# ATtinyTrafficLight.net
KiCad netlist of a schematic drawn in EAGLE
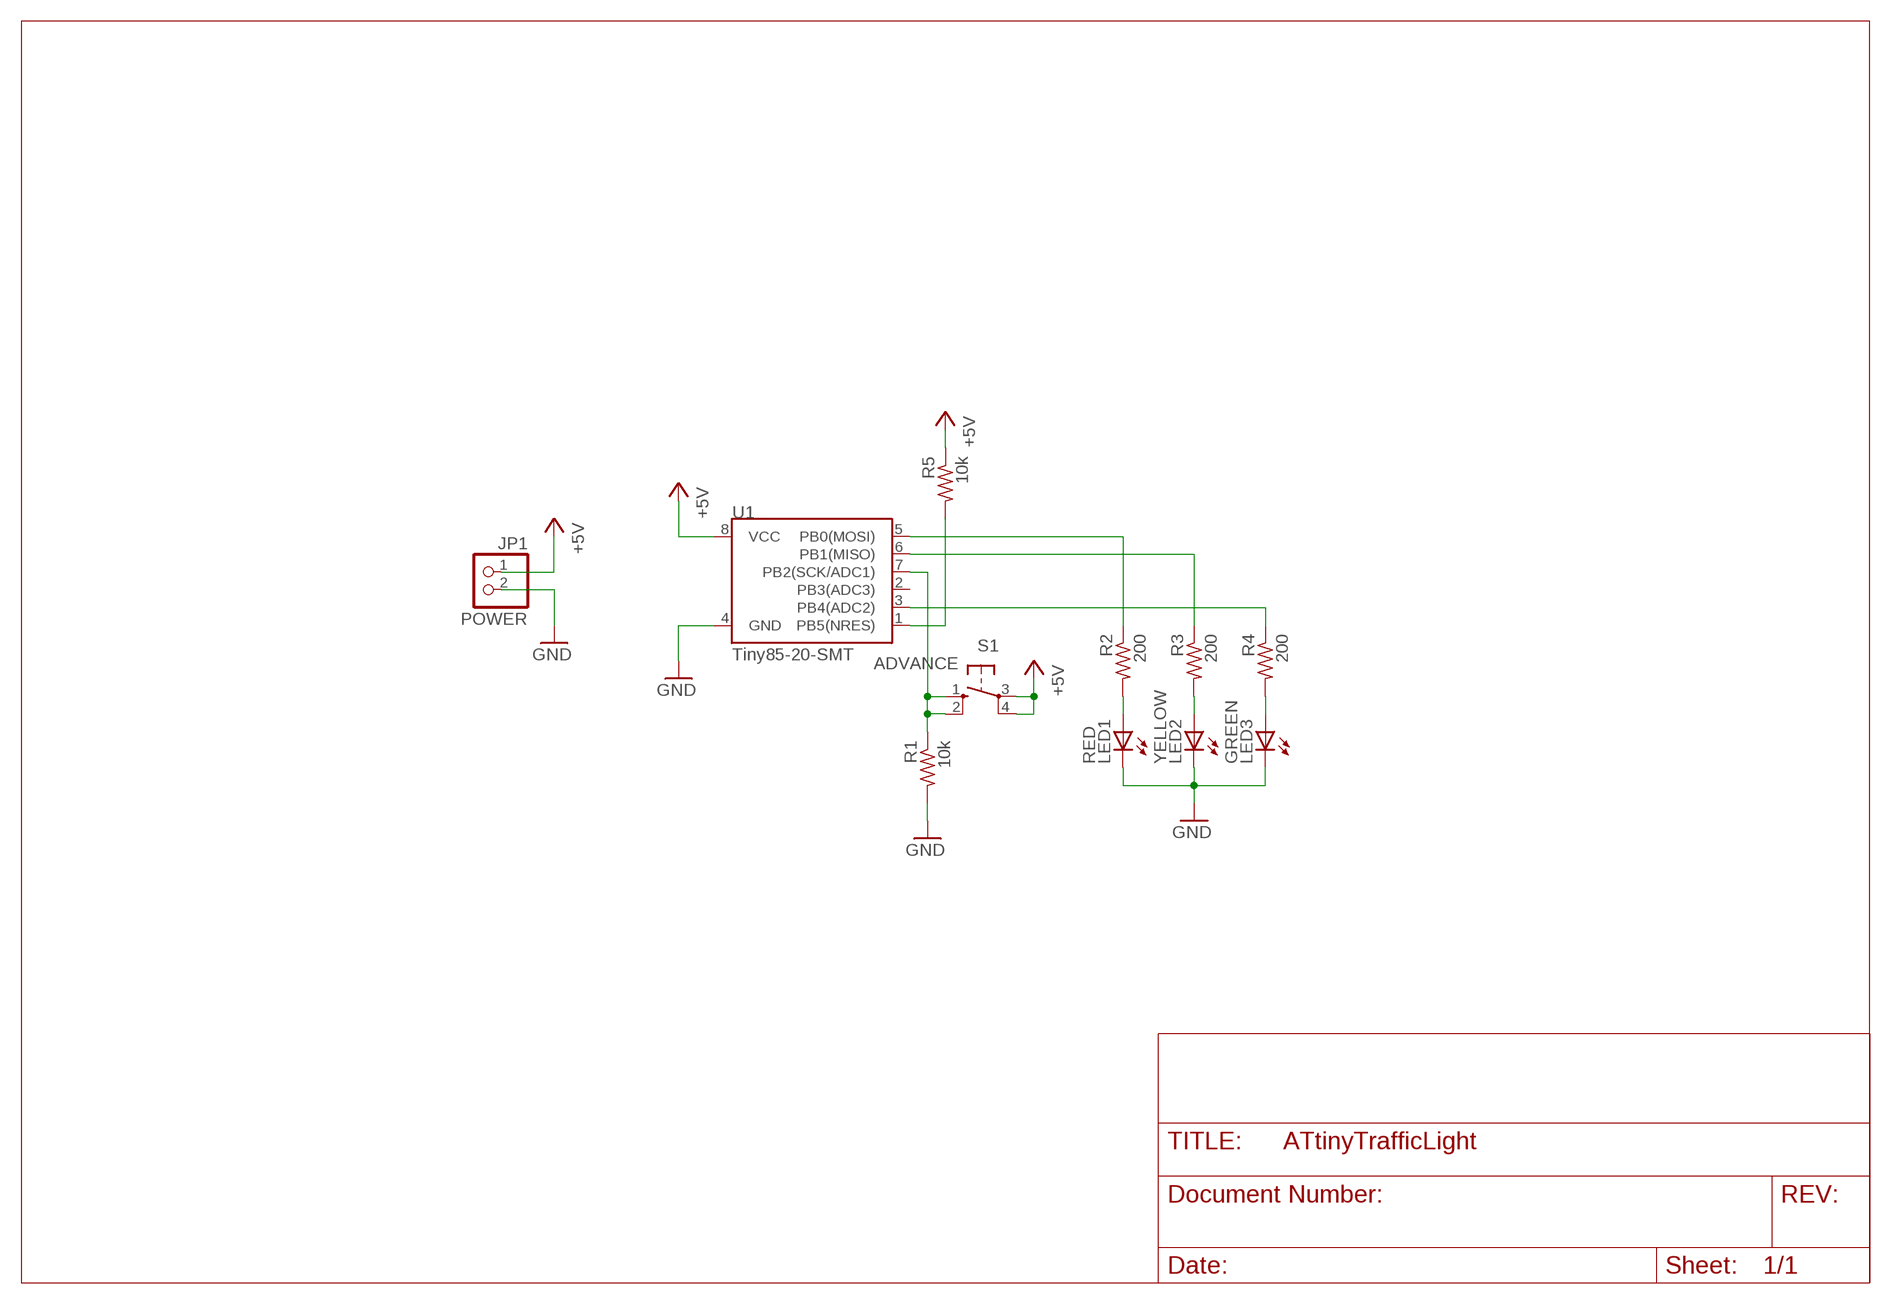
[diagram p0: schematic, sheet 1]

(export (version "E")
  (design (tool "Eeschema 10.0.6"))
  (components
    (comp (ref "JP1")
      (value "POWER")
      (footprint "eagle-import:1X02")
      (libsource (lib "eagle-import") (part "PINHD-1X2"))
    )
    (comp (ref "LED1")
      (value "RED")
      (footprint "eagle-import:CHIPLED_0805")
      (libsource (lib "eagle-import") (part "LEDCHIPLED_0805"))
    )
    (comp (ref "LED2")
      (value "YELLOW")
      (footprint "eagle-import:CHIPLED_0805")
      (libsource (lib "eagle-import") (part "LEDCHIPLED_0805"))
    )
    (comp (ref "LED3")
      (value "GREEN")
      (footprint "eagle-import:CHIPLED_0805")
      (libsource (lib "eagle-import") (part "LEDCHIPLED_0805"))
    )
    (comp (ref "R1")
      (value "10k")
      (footprint "eagle-import:R0805")
      (libsource (lib "eagle-import") (part "R-US_R0805"))
    )
    (comp (ref "R2")
      (value "200")
      (footprint "eagle-import:R0805")
      (libsource (lib "eagle-import") (part "R-US_R0805"))
    )
    (comp (ref "R3")
      (value "200")
      (footprint "eagle-import:R0805")
      (libsource (lib "eagle-import") (part "R-US_R0805"))
    )
    (comp (ref "R4")
      (value "200")
      (footprint "eagle-import:R0805")
      (libsource (lib "eagle-import") (part "R-US_R0805"))
    )
    (comp (ref "R5")
      (value "10k")
      (footprint "eagle-import:R0805")
      (libsource (lib "eagle-import") (part "R-US_R0805"))
    )
    (comp (ref "S1")
      (value "ADVANCE")
      (footprint "eagle-import:B3F-10XX")
      (fields (field (name "MPN") "B3F-1000"))
      (libsource (lib "eagle-import") (part "10-XX"))
    )
    (comp (ref "U1")
      (value "Tiny85-20-SMT")
      (footprint "eagle-import:SO08-EIAJ")
      (libsource (lib "eagle-import") (part "ATTINY45TINY85-20-SMT"))
    )
  )
  (nets
    (net (code "1") (name "+5V") (class "Default")
      (node (ref "JP1") (pin "1") (pinfunction "1_1") (pintype "passive"))
      (node (ref "R5") (pin "1") (pinfunction "1_1") (pintype "passive"))
      (node (ref "S1") (pin "3") (pinfunction "P_3") (pintype "passive"))
      (node (ref "S1") (pin "4") (pinfunction "P1_4") (pintype "passive"))
      (node (ref "U1") (pin "8") (pinfunction "VCC_8") (pintype "bidirectional"))
    )
    (net (code "2") (name "GND") (class "Default")
      (node (ref "JP1") (pin "2") (pinfunction "2_2") (pintype "passive"))
      (node (ref "LED1") (pin "C") (pinfunction "C_C") (pintype "passive"))
      (node (ref "LED2") (pin "C") (pinfunction "C_C") (pintype "passive"))
      (node (ref "LED3") (pin "C") (pinfunction "C_C") (pintype "passive"))
      (node (ref "R1") (pin "2") (pinfunction "2_2") (pintype "passive"))
      (node (ref "U1") (pin "4") (pinfunction "GND_4") (pintype "bidirectional"))
    )
    (net (code "3") (name "Net-(LED1-PadA)") (class "Default")
      (node (ref "LED1") (pin "A") (pinfunction "A_A") (pintype "passive"))
      (node (ref "R2") (pin "2") (pinfunction "2_2") (pintype "passive"))
    )
    (net (code "4") (name "Net-(LED2-PadA)") (class "Default")
      (node (ref "LED2") (pin "A") (pinfunction "A_A") (pintype "passive"))
      (node (ref "R3") (pin "2") (pinfunction "2_2") (pintype "passive"))
    )
    (net (code "5") (name "Net-(LED3-PadA)") (class "Default")
      (node (ref "LED3") (pin "A") (pinfunction "A_A") (pintype "passive"))
      (node (ref "R4") (pin "2") (pinfunction "2_2") (pintype "passive"))
    )
    (net (code "6") (name "Net-(S1-S)") (class "Default")
      (node (ref "R1") (pin "1") (pinfunction "1_1") (pintype "passive"))
      (node (ref "S1") (pin "1") (pinfunction "S_1") (pintype "passive"))
      (node (ref "S1") (pin "2") (pinfunction "S1_2") (pintype "passive"))
      (node (ref "U1") (pin "7") (pinfunction "PB2(SCK/ADC1)_7") (pintype "bidirectional"))
    )
    (net (code "7") (name "Net-(U1-PB0(MOSI))") (class "Default")
      (node (ref "R2") (pin "1") (pinfunction "1_1") (pintype "passive"))
      (node (ref "U1") (pin "5") (pinfunction "PB0(MOSI)_5") (pintype "bidirectional"))
    )
    (net (code "8") (name "Net-(U1-PB1(MISO))") (class "Default")
      (node (ref "R3") (pin "1") (pinfunction "1_1") (pintype "passive"))
      (node (ref "U1") (pin "6") (pinfunction "PB1(MISO)_6") (pintype "bidirectional"))
    )
    (net (code "9") (name "Net-(U1-PB4(ADC2))") (class "Default")
      (node (ref "R4") (pin "1") (pinfunction "1_1") (pintype "passive"))
      (node (ref "U1") (pin "3") (pinfunction "PB4(ADC2)_3") (pintype "bidirectional"))
    )
    (net (code "10") (name "Net-(U1-PB5(NRES))") (class "Default")
      (node (ref "R5") (pin "2") (pinfunction "2_2") (pintype "passive"))
      (node (ref "U1") (pin "1") (pinfunction "PB5(NRES)_1") (pintype "bidirectional"))
    )
    (net (code "11") (name "unconnected-(U1-PB3(ADC3)-Pad2)") (class "Default")
      (node (ref "U1") (pin "2") (pinfunction "PB3(ADC3)_2") (pintype "bidirectional"))
    )
  )
)
